# QuadPFets.net
KiCad netlist of a schematic drawn in EAGLE
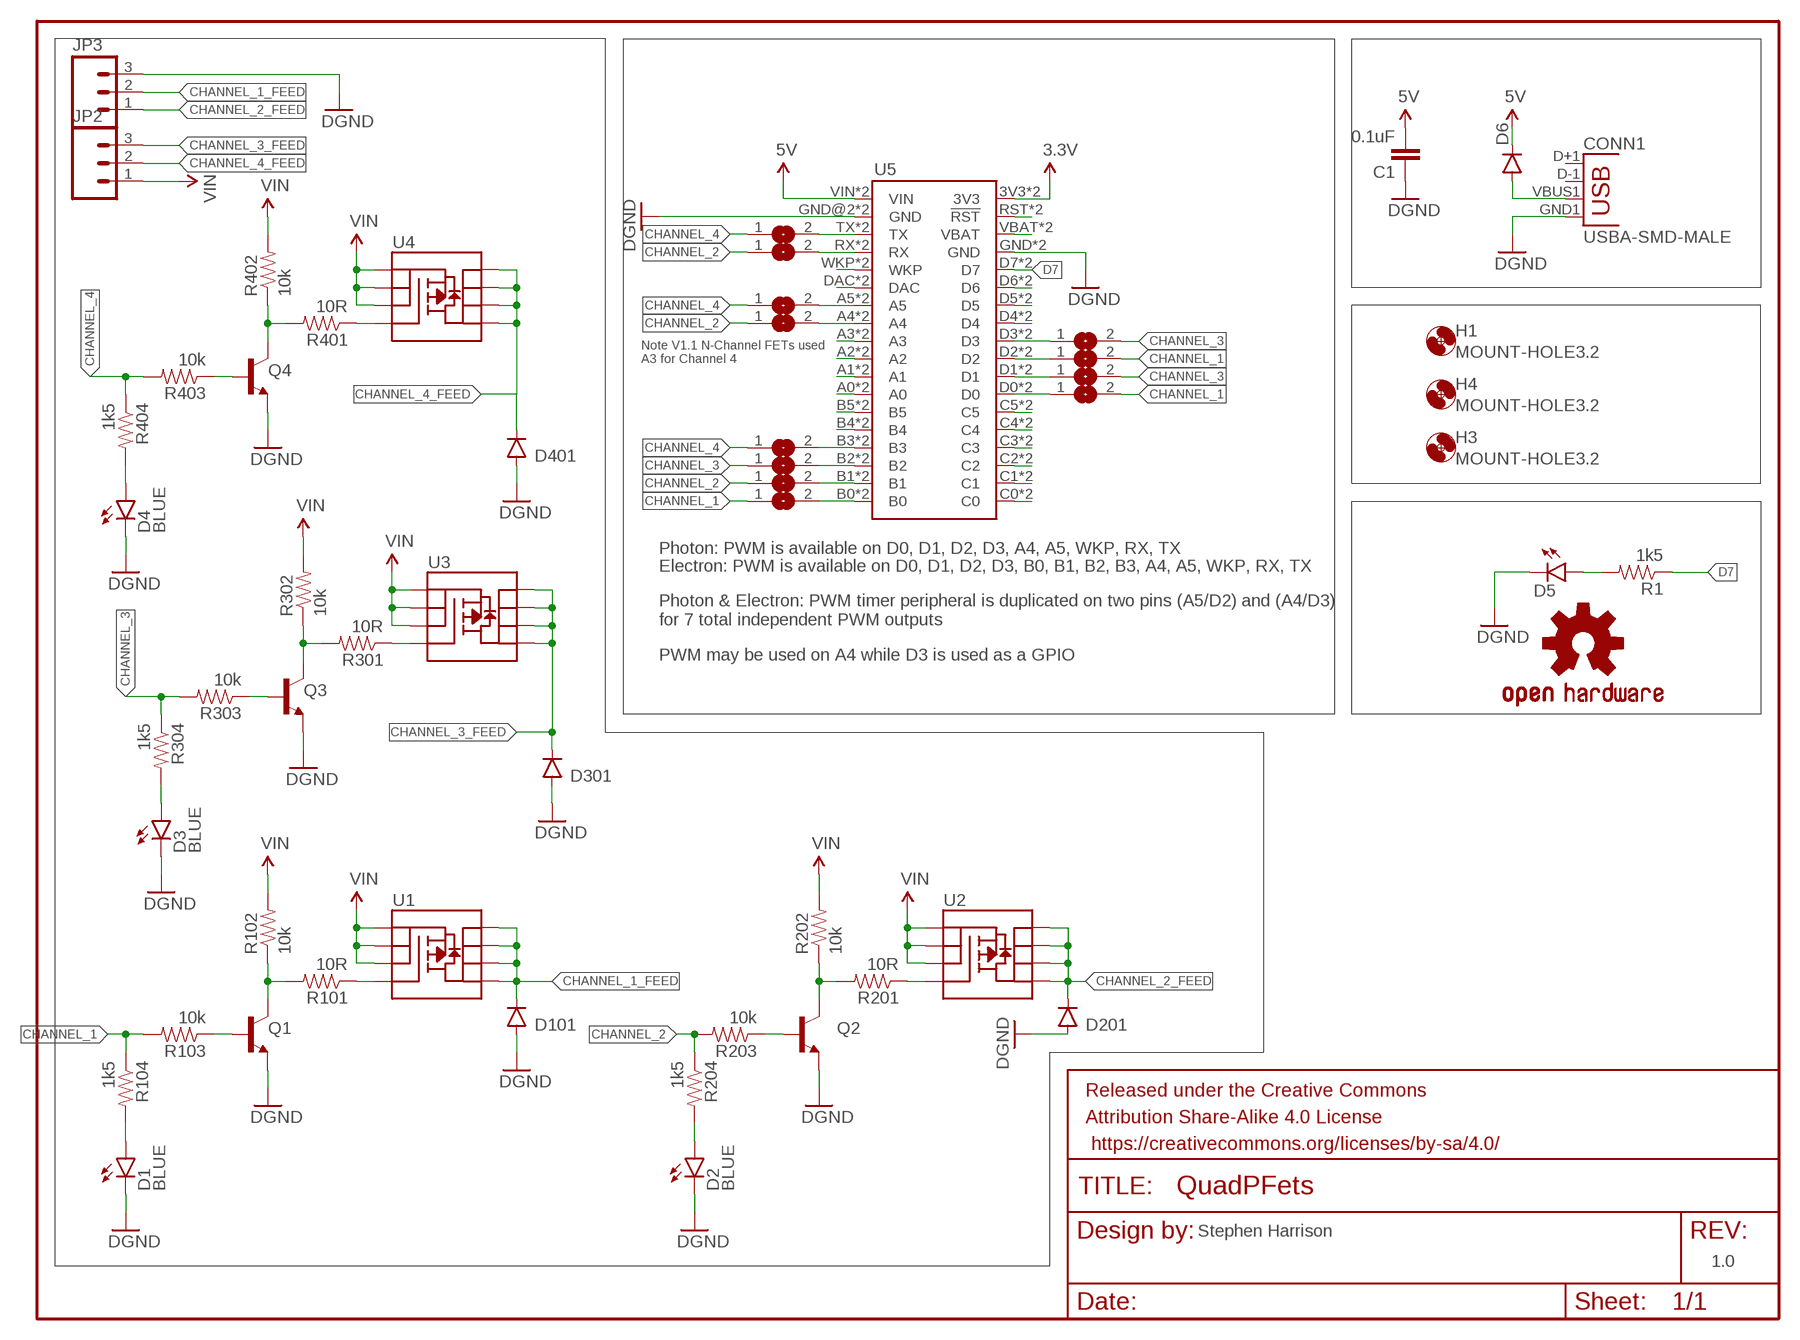
[diagram p0: schematic, sheet 1]

(export (version "E")
  (design (tool "Eeschema 10.0.6"))
  (components
    (comp (ref "C1")
      (value "0.1uF")
      (footprint "eagle-import:0805")
      (libsource (lib "eagle-import") (part "CAP0805"))
    )
    (comp (ref "CONN1")
      (value "USBA-SMD-MALE")
      (footprint "eagle-import:USB-A-SMT-MALE")
      (libsource (lib "eagle-import") (part "USBA-SMD-MALE"))
    )
    (comp (ref "D1")
      (value "BLUE")
      (footprint "eagle-import:LED-1206")
      (libsource (lib "eagle-import") (part "LED-BLUE1206"))
    )
    (comp (ref "D2")
      (value "BLUE")
      (footprint "eagle-import:LED-1206")
      (libsource (lib "eagle-import") (part "LED-BLUE1206"))
    )
    (comp (ref "D3")
      (value "BLUE")
      (footprint "eagle-import:LED-1206")
      (libsource (lib "eagle-import") (part "LED-BLUE1206"))
    )
    (comp (ref "D4")
      (value "BLUE")
      (footprint "eagle-import:LED-1206")
      (libsource (lib "eagle-import") (part "LED-BLUE1206"))
    )
    (comp (ref "D5")
      (value "LED1206-BOTTOM")
      (footprint "eagle-import:LED-1206-BOTTOM")
      (libsource (lib "eagle-import") (part "LED1206-BOTTOM"))
    )
    (comp (ref "D6")
      (value "DIODESMA")
      (footprint "eagle-import:SMA-DIODE")
      (libsource (lib "eagle-import") (part "DIODESMA"))
    )
    (comp (ref "D101")
      (value "DIODESOD123")
      (footprint "eagle-import:SOD-123")
      (libsource (lib "eagle-import") (part "DIODESOD123"))
    )
    (comp (ref "D201")
      (value "DIODESOD123")
      (footprint "eagle-import:SOD-123")
      (libsource (lib "eagle-import") (part "DIODESOD123"))
    )
    (comp (ref "D301")
      (value "DIODESOD123")
      (footprint "eagle-import:SOD-123")
      (libsource (lib "eagle-import") (part "DIODESOD123"))
    )
    (comp (ref "D401")
      (value "DIODESOD123")
      (footprint "eagle-import:SOD-123")
      (libsource (lib "eagle-import") (part "DIODESOD123"))
    )
    (comp (ref "FRAME2")
      (value "FRAME-LETTER")
      (footprint "eagle-import:CREATIVE_COMMONS")
      (libsource (lib "eagle-import") (part "FRAME-LETTER"))
    )
    (comp (ref "H1")
      (value "MOUNT-HOLE3.2")
      (footprint "eagle-import:3,2")
      (libsource (lib "eagle-import") (part "MOUNT-HOLE3.2"))
    )
    (comp (ref "H3")
      (value "MOUNT-HOLE3.2")
      (footprint "eagle-import:3,2")
      (libsource (lib "eagle-import") (part "MOUNT-HOLE3.2"))
    )
    (comp (ref "H4")
      (value "MOUNT-HOLE3.2")
      (footprint "eagle-import:3,2")
      (libsource (lib "eagle-import") (part "MOUNT-HOLE3.2"))
    )
    (comp (ref "JP2")
      (value "M03-SCREW-5MM")
      (footprint "eagle-import:SCREWTERMINAL-5MM-3")
      (libsource (lib "eagle-import") (part "M03-SCREW-5MM"))
    )
    (comp (ref "JP3")
      (value "M03-SCREW-5MM")
      (footprint "eagle-import:SCREWTERMINAL-5MM-3")
      (libsource (lib "eagle-import") (part "M03-SCREW-5MM"))
    )
    (comp (ref "LOGO1")
      (value "OSHW-LOGOM")
      (footprint "eagle-import:OSHW-LOGO-M")
      (libsource (lib "eagle-import") (part "OSHW-LOGOM"))
    )
    (comp (ref "Q1")
      (value "BC817-40SMD")
      (footprint "eagle-import:SOT23-BEC")
      (libsource (lib "eagle-import") (part "BC817SMD-40"))
    )
    (comp (ref "Q2")
      (value "BC817-40SMD")
      (footprint "eagle-import:SOT23-BEC")
      (libsource (lib "eagle-import") (part "BC817SMD-40"))
    )
    (comp (ref "Q3")
      (value "BC817-40SMD")
      (footprint "eagle-import:SOT23-BEC")
      (libsource (lib "eagle-import") (part "BC817SMD-40"))
    )
    (comp (ref "Q4")
      (value "BC817-40SMD")
      (footprint "eagle-import:SOT23-BEC")
      (libsource (lib "eagle-import") (part "BC817SMD-40"))
    )
    (comp (ref "R1")
      (value "1k5")
      (footprint "eagle-import:0805")
      (libsource (lib "eagle-import") (part "RESISTOR0805-RES"))
    )
    (comp (ref "R101")
      (value "10R")
      (footprint "eagle-import:0805")
      (libsource (lib "eagle-import") (part "RESISTOR0805-RES"))
    )
    (comp (ref "R102")
      (value "10k")
      (footprint "eagle-import:0805")
      (libsource (lib "eagle-import") (part "RESISTOR0805-RES"))
    )
    (comp (ref "R103")
      (value "10k")
      (footprint "eagle-import:0805")
      (libsource (lib "eagle-import") (part "RESISTOR0805-RES"))
    )
    (comp (ref "R104")
      (value "1k5")
      (footprint "eagle-import:0805")
      (libsource (lib "eagle-import") (part "RESISTOR0805-RES"))
    )
    (comp (ref "R201")
      (value "10R")
      (footprint "eagle-import:0805")
      (libsource (lib "eagle-import") (part "RESISTOR0805-RES"))
    )
    (comp (ref "R202")
      (value "10k")
      (footprint "eagle-import:0805")
      (libsource (lib "eagle-import") (part "RESISTOR0805-RES"))
    )
    (comp (ref "R203")
      (value "10k")
      (footprint "eagle-import:0805")
      (libsource (lib "eagle-import") (part "RESISTOR0805-RES"))
    )
    (comp (ref "R204")
      (value "1k5")
      (footprint "eagle-import:0805")
      (libsource (lib "eagle-import") (part "RESISTOR0805-RES"))
    )
    (comp (ref "R301")
      (value "10R")
      (footprint "eagle-import:0805")
      (libsource (lib "eagle-import") (part "RESISTOR0805-RES"))
    )
    (comp (ref "R302")
      (value "10k")
      (footprint "eagle-import:0805")
      (libsource (lib "eagle-import") (part "RESISTOR0805-RES"))
    )
    (comp (ref "R303")
      (value "10k")
      (footprint "eagle-import:0805")
      (libsource (lib "eagle-import") (part "RESISTOR0805-RES"))
    )
    (comp (ref "R304")
      (value "1k5")
      (footprint "eagle-import:0805")
      (libsource (lib "eagle-import") (part "RESISTOR0805-RES"))
    )
    (comp (ref "R401")
      (value "10R")
      (footprint "eagle-import:0805")
      (libsource (lib "eagle-import") (part "RESISTOR0805-RES"))
    )
    (comp (ref "R402")
      (value "10k")
      (footprint "eagle-import:0805")
      (libsource (lib "eagle-import") (part "RESISTOR0805-RES"))
    )
    (comp (ref "R403")
      (value "10k")
      (footprint "eagle-import:0805")
      (libsource (lib "eagle-import") (part "RESISTOR0805-RES"))
    )
    (comp (ref "R404")
      (value "1k5")
      (footprint "eagle-import:0805")
      (libsource (lib "eagle-import") (part "RESISTOR0805-RES"))
    )
    (comp (ref "SJ1") (value "SJ") (footprint "eagle-import:SJ") (libsource (lib "eagle-import") (part "SJ")))
    (comp (ref "SJ2") (value "SJ") (footprint "eagle-import:SJ") (libsource (lib "eagle-import") (part "SJ")))
    (comp (ref "SJ3") (value "SJ") (footprint "eagle-import:SJ") (libsource (lib "eagle-import") (part "SJ")))
    (comp (ref "SJ4") (value "SJ") (footprint "eagle-import:SJ") (libsource (lib "eagle-import") (part "SJ")))
    (comp (ref "SJ5") (value "SJ") (footprint "eagle-import:SJ") (libsource (lib "eagle-import") (part "SJ")))
    (comp (ref "SJ6") (value "SJ") (footprint "eagle-import:SJ") (libsource (lib "eagle-import") (part "SJ")))
    (comp (ref "SJ7") (value "SJ") (footprint "eagle-import:SJ") (libsource (lib "eagle-import") (part "SJ")))
    (comp (ref "SJ8") (value "SJ") (footprint "eagle-import:SJ") (libsource (lib "eagle-import") (part "SJ")))
    (comp (ref "SJ9") (value "SJ") (footprint "eagle-import:SJ") (libsource (lib "eagle-import") (part "SJ")))
    (comp (ref "SJ10")
      (value "SJ")
      (footprint "eagle-import:SJ")
      (libsource (lib "eagle-import") (part "SJ"))
    )
    (comp (ref "SJ11")
      (value "SJ")
      (footprint "eagle-import:SJ")
      (libsource (lib "eagle-import") (part "SJ"))
    )
    (comp (ref "SJ12")
      (value "SJ")
      (footprint "eagle-import:SJ")
      (libsource (lib "eagle-import") (part "SJ"))
    )
    (comp (ref "U1")
      (value "MOSFET-PCHANNEL-SOIC8SOIC8")
      (footprint "eagle-import:SO08")
      (libsource (lib "eagle-import") (part "MOSFET-PCHANNEL-SOIC8SOIC8"))
    )
    (comp (ref "U2")
      (value "MOSFET-PCHANNEL-SOIC8SOIC8")
      (footprint "eagle-import:SO08")
      (libsource (lib "eagle-import") (part "MOSFET-PCHANNEL-SOIC8SOIC8"))
    )
    (comp (ref "U3")
      (value "MOSFET-PCHANNEL-SOIC8SOIC8")
      (footprint "eagle-import:SO08")
      (libsource (lib "eagle-import") (part "MOSFET-PCHANNEL-SOIC8SOIC8"))
    )
    (comp (ref "U4")
      (value "MOSFET-PCHANNEL-SOIC8SOIC8")
      (footprint "eagle-import:SO08")
      (libsource (lib "eagle-import") (part "MOSFET-PCHANNEL-SOIC8SOIC8"))
    )
    (comp (ref "U5")
      (value "ELECTRONDUALNAMED")
      (footprint "eagle-import:ELECTRON_SIMPLE_SILK_NAMES_DUAL")
      (libsource (lib "eagle-import") (part "ELECTRONDUALNAMED"))
    )
  )
  (nets
    (net (code "1") (name "3.3V") (class "Default")
      (node (ref "U5") (pin "3V3") (pinfunction "3V3_3V3") (pintype "power_in"))
      (node (ref "U5") (pin "3V3_1") (pinfunction "3V3_3V3_1") (pintype "power_in"))
    )
    (net (code "2") (name "5V") (class "Default")
      (node (ref "C1") (pin "2") (pinfunction "2_2") (pintype "passive"))
      (node (ref "D6") (pin "C") (pinfunction "C_C") (pintype "passive"))
      (node (ref "U5") (pin "VIN") (pinfunction "VIN_VIN") (pintype "power_in"))
      (node (ref "U5") (pin "VIN_1B") (pinfunction "VIN_VIN_1B") (pintype "power_in"))
    )
    (net (code "3") (name "CHANNEL_1") (class "Default")
      (node (ref "R103") (pin "2") (pinfunction "2_2") (pintype "passive"))
      (node (ref "R104") (pin "1") (pinfunction "1_1") (pintype "passive"))
      (node (ref "SJ11") (pin "2") (pinfunction "2_2") (pintype "passive"))
      (node (ref "SJ4") (pin "1") (pinfunction "1_1") (pintype "passive"))
      (node (ref "SJ5") (pin "2") (pinfunction "2_2") (pintype "passive"))
    )
    (net (code "4") (name "CHANNEL_1_FEED") (class "Default")
      (node (ref "D101") (pin "C") (pinfunction "C_C") (pintype "passive"))
      (node (ref "JP3") (pin "2") (pinfunction "2_2") (pintype "passive"))
      (node (ref "U1") (pin "5") (pinfunction "D_5") (pintype "bidirectional"))
      (node (ref "U1") (pin "6") (pinfunction "D_6") (pintype "bidirectional"))
      (node (ref "U1") (pin "7") (pinfunction "D_7") (pintype "bidirectional"))
      (node (ref "U1") (pin "8") (pinfunction "D_8") (pintype "bidirectional"))
    )
    (net (code "5") (name "CHANNEL_2") (class "Default")
      (node (ref "R203") (pin "2") (pinfunction "2_2") (pintype "passive"))
      (node (ref "R204") (pin "1") (pinfunction "1_1") (pintype "passive"))
      (node (ref "SJ10") (pin "1") (pinfunction "1_1") (pintype "passive"))
      (node (ref "SJ3") (pin "1") (pinfunction "1_1") (pintype "passive"))
      (node (ref "SJ8") (pin "1") (pinfunction "1_1") (pintype "passive"))
    )
    (net (code "6") (name "CHANNEL_2_FEED") (class "Default")
      (node (ref "D201") (pin "C") (pinfunction "C_C") (pintype "passive"))
      (node (ref "JP3") (pin "1") (pinfunction "1_1") (pintype "passive"))
      (node (ref "U2") (pin "5") (pinfunction "D_5") (pintype "bidirectional"))
      (node (ref "U2") (pin "6") (pinfunction "D_6") (pintype "bidirectional"))
      (node (ref "U2") (pin "7") (pinfunction "D_7") (pintype "bidirectional"))
      (node (ref "U2") (pin "8") (pinfunction "D_8") (pintype "bidirectional"))
    )
    (net (code "7") (name "CHANNEL_3") (class "Default")
      (node (ref "R303") (pin "2") (pinfunction "2_2") (pintype "passive"))
      (node (ref "R304") (pin "1") (pinfunction "1_1") (pintype "passive"))
      (node (ref "SJ12") (pin "2") (pinfunction "2_2") (pintype "passive"))
      (node (ref "SJ2") (pin "1") (pinfunction "1_1") (pintype "passive"))
      (node (ref "SJ6") (pin "2") (pinfunction "2_2") (pintype "passive"))
    )
    (net (code "8") (name "CHANNEL_3_FEED") (class "Default")
      (node (ref "D301") (pin "C") (pinfunction "C_C") (pintype "passive"))
      (node (ref "JP2") (pin "3") (pinfunction "3_3") (pintype "passive"))
      (node (ref "U3") (pin "5") (pinfunction "D_5") (pintype "bidirectional"))
      (node (ref "U3") (pin "6") (pinfunction "D_6") (pintype "bidirectional"))
      (node (ref "U3") (pin "7") (pinfunction "D_7") (pintype "bidirectional"))
      (node (ref "U3") (pin "8") (pinfunction "D_8") (pintype "bidirectional"))
    )
    (net (code "9") (name "CHANNEL_4") (class "Default")
      (node (ref "R403") (pin "2") (pinfunction "2_2") (pintype "passive"))
      (node (ref "R404") (pin "1") (pinfunction "1_1") (pintype "passive"))
      (node (ref "SJ1") (pin "1") (pinfunction "1_1") (pintype "passive"))
      (node (ref "SJ7") (pin "1") (pinfunction "1_1") (pintype "passive"))
      (node (ref "SJ9") (pin "1") (pinfunction "1_1") (pintype "passive"))
    )
    (net (code "10") (name "CHANNEL_4_FEED") (class "Default")
      (node (ref "D401") (pin "C") (pinfunction "C_C") (pintype "passive"))
      (node (ref "JP2") (pin "2") (pinfunction "2_2") (pintype "passive"))
      (node (ref "U4") (pin "5") (pinfunction "D_5") (pintype "bidirectional"))
      (node (ref "U4") (pin "6") (pinfunction "D_6") (pintype "bidirectional"))
      (node (ref "U4") (pin "7") (pinfunction "D_7") (pintype "bidirectional"))
      (node (ref "U4") (pin "8") (pinfunction "D_8") (pintype "bidirectional"))
    )
    (net (code "11") (name "D7") (class "Default")
      (node (ref "R1") (pin "1") (pinfunction "1_1") (pintype "passive"))
      (node (ref "U5") (pin "D7") (pinfunction "D7_D7") (pintype "bidirectional"))
      (node (ref "U5") (pin "D7_1") (pinfunction "D7_D7_1") (pintype "bidirectional"))
    )
    (net (code "12") (name "DGND") (class "Default")
      (node (ref "C1") (pin "1") (pinfunction "1_1") (pintype "passive"))
      (node (ref "CONN1") (pin "GND1") (pinfunction "GND_GND1") (pintype "bidirectional"))
      (node (ref "D1") (pin "C") (pinfunction "C_C") (pintype "passive"))
      (node (ref "D101") (pin "A") (pinfunction "A_A") (pintype "passive"))
      (node (ref "D2") (pin "C") (pinfunction "C_C") (pintype "passive"))
      (node (ref "D201") (pin "A") (pinfunction "A_A") (pintype "passive"))
      (node (ref "D3") (pin "C") (pinfunction "C_C") (pintype "passive"))
      (node (ref "D301") (pin "A") (pinfunction "A_A") (pintype "passive"))
      (node (ref "D4") (pin "C") (pinfunction "C_C") (pintype "passive"))
      (node (ref "D401") (pin "A") (pinfunction "A_A") (pintype "passive"))
      (node (ref "D5") (pin "C") (pinfunction "C_C") (pintype "passive"))
      (node (ref "JP3") (pin "3") (pinfunction "3_3") (pintype "passive"))
      (node (ref "Q1") (pin "E") (pinfunction "E_E") (pintype "passive"))
      (node (ref "Q2") (pin "E") (pinfunction "E_E") (pintype "passive"))
      (node (ref "Q3") (pin "E") (pinfunction "E_E") (pintype "passive"))
      (node (ref "Q4") (pin "E") (pinfunction "E_E") (pintype "passive"))
      (node (ref "U5") (pin "GND") (pinfunction "GND_GND") (pintype "power_in"))
      (node (ref "U5") (pin "GND@2") (pinfunction "GND_GND@2") (pintype "power_in"))
      (node (ref "U5") (pin "GND_1") (pinfunction "GND_GND_1") (pintype "power_in"))
      (node (ref "U5") (pin "GND_1B") (pinfunction "GND_GND_1B") (pintype "power_in"))
    )
    (net (code "13") (name "Net-(CONN1-VBUS)") (class "Default")
      (node (ref "CONN1") (pin "VBUS1") (pinfunction "VBUS_VBUS1") (pintype "bidirectional"))
      (node (ref "D6") (pin "A") (pinfunction "A_A") (pintype "passive"))
    )
    (net (code "14") (name "Net-(D1-PadA)") (class "Default")
      (node (ref "D1") (pin "A") (pinfunction "A_A") (pintype "passive"))
      (node (ref "R104") (pin "2") (pinfunction "2_2") (pintype "passive"))
    )
    (net (code "15") (name "Net-(D2-PadA)") (class "Default")
      (node (ref "D2") (pin "A") (pinfunction "A_A") (pintype "passive"))
      (node (ref "R204") (pin "2") (pinfunction "2_2") (pintype "passive"))
    )
    (net (code "16") (name "Net-(D3-PadA)") (class "Default")
      (node (ref "D3") (pin "A") (pinfunction "A_A") (pintype "passive"))
      (node (ref "R304") (pin "2") (pinfunction "2_2") (pintype "passive"))
    )
    (net (code "17") (name "Net-(D4-PadA)") (class "Default")
      (node (ref "D4") (pin "A") (pinfunction "A_A") (pintype "passive"))
      (node (ref "R404") (pin "2") (pinfunction "2_2") (pintype "passive"))
    )
    (net (code "18") (name "Net-(D5-PadA)") (class "Default")
      (node (ref "D5") (pin "A") (pinfunction "A_A") (pintype "passive"))
      (node (ref "R1") (pin "2") (pinfunction "2_2") (pintype "passive"))
    )
    (net (code "19") (name "Net-(Q1-PadB)") (class "Default")
      (node (ref "Q1") (pin "B") (pinfunction "B_B") (pintype "passive"))
      (node (ref "R103") (pin "1") (pinfunction "1_1") (pintype "passive"))
    )
    (net (code "20") (name "Net-(Q1-PadC)") (class "Default")
      (node (ref "Q1") (pin "C") (pinfunction "C_C") (pintype "passive"))
      (node (ref "R101") (pin "2") (pinfunction "2_2") (pintype "passive"))
      (node (ref "R102") (pin "1") (pinfunction "1_1") (pintype "passive"))
    )
    (net (code "21") (name "Net-(Q2-PadB)") (class "Default")
      (node (ref "Q2") (pin "B") (pinfunction "B_B") (pintype "passive"))
      (node (ref "R203") (pin "1") (pinfunction "1_1") (pintype "passive"))
    )
    (net (code "22") (name "Net-(Q2-PadC)") (class "Default")
      (node (ref "Q2") (pin "C") (pinfunction "C_C") (pintype "passive"))
      (node (ref "R201") (pin "2") (pinfunction "2_2") (pintype "passive"))
      (node (ref "R202") (pin "1") (pinfunction "1_1") (pintype "passive"))
    )
    (net (code "23") (name "Net-(Q3-PadB)") (class "Default")
      (node (ref "Q3") (pin "B") (pinfunction "B_B") (pintype "passive"))
      (node (ref "R303") (pin "1") (pinfunction "1_1") (pintype "passive"))
    )
    (net (code "24") (name "Net-(Q3-PadC)") (class "Default")
      (node (ref "Q3") (pin "C") (pinfunction "C_C") (pintype "passive"))
      (node (ref "R301") (pin "2") (pinfunction "2_2") (pintype "passive"))
      (node (ref "R302") (pin "1") (pinfunction "1_1") (pintype "passive"))
    )
    (net (code "25") (name "Net-(Q4-PadB)") (class "Default")
      (node (ref "Q4") (pin "B") (pinfunction "B_B") (pintype "passive"))
      (node (ref "R403") (pin "1") (pinfunction "1_1") (pintype "passive"))
    )
    (net (code "26") (name "Net-(Q4-PadC)") (class "Default")
      (node (ref "Q4") (pin "C") (pinfunction "C_C") (pintype "passive"))
      (node (ref "R401") (pin "2") (pinfunction "2_2") (pintype "passive"))
      (node (ref "R402") (pin "1") (pinfunction "1_1") (pintype "passive"))
    )
    (net (code "27") (name "Net-(SJ1-Pad2)") (class "Default")
      (node (ref "SJ1") (pin "2") (pinfunction "2_2") (pintype "passive"))
      (node (ref "U5") (pin "B3") (pinfunction "B3_B3") (pintype "bidirectional"))
      (node (ref "U5") (pin "B3_1") (pinfunction "B3_B3_1") (pintype "bidirectional"))
    )
    (net (code "28") (name "Net-(SJ2-Pad2)") (class "Default")
      (node (ref "SJ2") (pin "2") (pinfunction "2_2") (pintype "passive"))
      (node (ref "U5") (pin "B2") (pinfunction "B2_B2") (pintype "bidirectional"))
      (node (ref "U5") (pin "B2_1") (pinfunction "B2_B2_1") (pintype "bidirectional"))
    )
    (net (code "29") (name "Net-(SJ3-Pad2)") (class "Default")
      (node (ref "SJ3") (pin "2") (pinfunction "2_2") (pintype "passive"))
      (node (ref "U5") (pin "B1") (pinfunction "B1_B1") (pintype "bidirectional"))
      (node (ref "U5") (pin "B1_1") (pinfunction "B1_B1_1") (pintype "bidirectional"))
    )
    (net (code "30") (name "Net-(SJ4-Pad2)") (class "Default")
      (node (ref "SJ4") (pin "2") (pinfunction "2_2") (pintype "passive"))
      (node (ref "U5") (pin "B0") (pinfunction "B0_B0") (pintype "bidirectional"))
      (node (ref "U5") (pin "B0_1") (pinfunction "B0_B0_1") (pintype "bidirectional"))
    )
    (net (code "31") (name "Net-(SJ5-Pad1)") (class "Default")
      (node (ref "SJ5") (pin "1") (pinfunction "1_1") (pintype "passive"))
      (node (ref "U5") (pin "D2") (pinfunction "D2_D2") (pintype "bidirectional"))
      (node (ref "U5") (pin "D2_1") (pinfunction "D2_D2_1") (pintype "bidirectional"))
    )
    (net (code "32") (name "Net-(SJ6-Pad1)") (class "Default")
      (node (ref "SJ6") (pin "1") (pinfunction "1_1") (pintype "passive"))
      (node (ref "U5") (pin "D3") (pinfunction "D3_D3") (pintype "bidirectional"))
      (node (ref "U5") (pin "D3_1") (pinfunction "D3_D3_1") (pintype "bidirectional"))
    )
    (net (code "33") (name "Net-(SJ7-Pad2)") (class "Default")
      (node (ref "SJ7") (pin "2") (pinfunction "2_2") (pintype "passive"))
      (node (ref "U5") (pin "TX") (pinfunction "TX_TX") (pintype "bidirectional"))
      (node (ref "U5") (pin "TX_1") (pinfunction "TX_TX_1") (pintype "bidirectional"))
    )
    (net (code "34") (name "Net-(SJ8-Pad2)") (class "Default")
      (node (ref "SJ8") (pin "2") (pinfunction "2_2") (pintype "passive"))
      (node (ref "U5") (pin "A4") (pinfunction "A4_A4") (pintype "bidirectional"))
      (node (ref "U5") (pin "A4_1") (pinfunction "A4_A4_1") (pintype "bidirectional"))
    )
    (net (code "35") (name "Net-(SJ9-Pad2)") (class "Default")
      (node (ref "SJ9") (pin "2") (pinfunction "2_2") (pintype "passive"))
      (node (ref "U5") (pin "A5") (pinfunction "A5_A5") (pintype "bidirectional"))
      (node (ref "U5") (pin "A5_1") (pinfunction "A5_A5_1") (pintype "bidirectional"))
    )
    (net (code "36") (name "Net-(SJ10-Pad2)") (class "Default")
      (node (ref "SJ10") (pin "2") (pinfunction "2_2") (pintype "passive"))
      (node (ref "U5") (pin "RX") (pinfunction "RX_RX") (pintype "bidirectional"))
      (node (ref "U5") (pin "RX_1") (pinfunction "RX_RX_1") (pintype "bidirectional"))
    )
    (net (code "37") (name "Net-(SJ11-Pad1)") (class "Default")
      (node (ref "SJ11") (pin "1") (pinfunction "1_1") (pintype "passive"))
      (node (ref "U5") (pin "D0") (pinfunction "D0_D0") (pintype "bidirectional"))
      (node (ref "U5") (pin "D0_1") (pinfunction "D0_D0_1") (pintype "bidirectional"))
    )
    (net (code "38") (name "Net-(SJ12-Pad1)") (class "Default")
      (node (ref "SJ12") (pin "1") (pinfunction "1_1") (pintype "passive"))
      (node (ref "U5") (pin "D1") (pinfunction "D1_D1") (pintype "bidirectional"))
      (node (ref "U5") (pin "D1_1") (pinfunction "D1_D1_1") (pintype "bidirectional"))
    )
    (net (code "39") (name "Net-(U1-G)") (class "Default")
      (node (ref "R101") (pin "1") (pinfunction "1_1") (pintype "passive"))
      (node (ref "U1") (pin "4") (pinfunction "G_4") (pintype "bidirectional"))
    )
    (net (code "40") (name "Net-(U2-G)") (class "Default")
      (node (ref "R201") (pin "1") (pinfunction "1_1") (pintype "passive"))
      (node (ref "U2") (pin "4") (pinfunction "G_4") (pintype "bidirectional"))
    )
    (net (code "41") (name "Net-(U3-G)") (class "Default")
      (node (ref "R301") (pin "1") (pinfunction "1_1") (pintype "passive"))
      (node (ref "U3") (pin "4") (pinfunction "G_4") (pintype "bidirectional"))
    )
    (net (code "42") (name "Net-(U4-G)") (class "Default")
      (node (ref "R401") (pin "1") (pinfunction "1_1") (pintype "passive"))
      (node (ref "U4") (pin "4") (pinfunction "G_4") (pintype "bidirectional"))
    )
    (net (code "43") (name "Net-(U5-A0-PadA0_1)") (class "Default")
      (node (ref "U5") (pin "A0") (pinfunction "A0_A0") (pintype "bidirectional"))
      (node (ref "U5") (pin "A0_1") (pinfunction "A0_A0_1") (pintype "bidirectional"))
    )
    (net (code "44") (name "Net-(U5-A1-PadA1_1)") (class "Default")
      (node (ref "U5") (pin "A1") (pinfunction "A1_A1") (pintype "bidirectional"))
      (node (ref "U5") (pin "A1_1") (pinfunction "A1_A1_1") (pintype "bidirectional"))
    )
    (net (code "45") (name "Net-(U5-A2-PadA2_1)") (class "Default")
      (node (ref "U5") (pin "A2") (pinfunction "A2_A2") (pintype "bidirectional"))
      (node (ref "U5") (pin "A2_1") (pinfunction "A2_A2_1") (pintype "bidirectional"))
    )
    (net (code "46") (name "Net-(U5-A3-PadA3_1)") (class "Default")
      (node (ref "U5") (pin "A3") (pinfunction "A3_A3") (pintype "bidirectional"))
      (node (ref "U5") (pin "A3_1") (pinfunction "A3_A3_1") (pintype "bidirectional"))
    )
    (net (code "47") (name "Net-(U5-B4-PadB4_1)") (class "Default")
      (node (ref "U5") (pin "B4") (pinfunction "B4_B4") (pintype "bidirectional"))
      (node (ref "U5") (pin "B4_1") (pinfunction "B4_B4_1") (pintype "bidirectional"))
    )
    (net (code "48") (name "Net-(U5-B5-PadB5_1)") (class "Default")
      (node (ref "U5") (pin "B5") (pinfunction "B5_B5") (pintype "bidirectional"))
      (node (ref "U5") (pin "B5_1") (pinfunction "B5_B5_1") (pintype "bidirectional"))
    )
    (net (code "49") (name "Net-(U5-C0-PadC0_1)") (class "Default")
      (node (ref "U5") (pin "C0") (pinfunction "C0_C0") (pintype "bidirectional"))
      (node (ref "U5") (pin "C0_1") (pinfunction "C0_C0_1") (pintype "bidirectional"))
    )
    (net (code "50") (name "Net-(U5-C1-PadC1_1)") (class "Default")
      (node (ref "U5") (pin "C1") (pinfunction "C1_C1") (pintype "bidirectional"))
      (node (ref "U5") (pin "C1_1") (pinfunction "C1_C1_1") (pintype "bidirectional"))
    )
    (net (code "51") (name "Net-(U5-C2-PadC2_1)") (class "Default")
      (node (ref "U5") (pin "C2") (pinfunction "C2_C2") (pintype "bidirectional"))
      (node (ref "U5") (pin "C2_1") (pinfunction "C2_C2_1") (pintype "bidirectional"))
    )
    (net (code "52") (name "Net-(U5-C3-PadC3_1)") (class "Default")
      (node (ref "U5") (pin "C3") (pinfunction "C3_C3") (pintype "bidirectional"))
      (node (ref "U5") (pin "C3_1") (pinfunction "C3_C3_1") (pintype "bidirectional"))
    )
    (net (code "53") (name "Net-(U5-C4-PadC4_1)") (class "Default")
      (node (ref "U5") (pin "C4") (pinfunction "C4_C4") (pintype "bidirectional"))
      (node (ref "U5") (pin "C4_1") (pinfunction "C4_C4_1") (pintype "bidirectional"))
    )
    (net (code "54") (name "Net-(U5-C5-PadC5_1)") (class "Default")
      (node (ref "U5") (pin "C5") (pinfunction "C5_C5") (pintype "bidirectional"))
      (node (ref "U5") (pin "C5_1") (pinfunction "C5_C5_1") (pintype "bidirectional"))
    )
    (net (code "55") (name "Net-(U5-D4-PadD4_1)") (class "Default")
      (node (ref "U5") (pin "D4") (pinfunction "D4_D4") (pintype "bidirectional"))
      (node (ref "U5") (pin "D4_1") (pinfunction "D4_D4_1") (pintype "bidirectional"))
    )
    (net (code "56") (name "Net-(U5-D5-PadD5_1)") (class "Default")
      (node (ref "U5") (pin "D5") (pinfunction "D5_D5") (pintype "bidirectional"))
      (node (ref "U5") (pin "D5_1") (pinfunction "D5_D5_1") (pintype "bidirectional"))
    )
    (net (code "57") (name "Net-(U5-D6-PadD6_1)") (class "Default")
      (node (ref "U5") (pin "D6") (pinfunction "D6_D6") (pintype "bidirectional"))
      (node (ref "U5") (pin "D6_1") (pinfunction "D6_D6_1") (pintype "bidirectional"))
    )
    (net (code "58") (name "Net-(U5-DAC-PadDAC_1)") (class "Default")
      (node (ref "U5") (pin "DAC") (pinfunction "DAC_DAC") (pintype "bidirectional"))
      (node (ref "U5") (pin "DAC_1") (pinfunction "DAC_DAC_1") (pintype "bidirectional"))
    )
    (net (code "59") (name "Net-(U5-PadVBAT)") (class "Default")
      (node (ref "U5") (pin "VBAT") (pinfunction "VBAT_VBAT") (pintype "passive"))
      (node (ref "U5") (pin "VBATT_1") (pinfunction "VBAT_VBATT_1") (pintype "passive"))
    )
    (net (code "60") (name "Net-(U5-PadWKP)") (class "Default")
      (node (ref "U5") (pin "WKP") (pinfunction "WKP_WKP") (pintype "bidirectional"))
      (node (ref "U5") (pin "WKP_1") (pinfunction "WKP_WKP_1") (pintype "bidirectional"))
    )
    (net (code "61") (name "Net-(U5-~{RST}-PadRST)") (class "Default")
      (node (ref "U5") (pin "RST") (pinfunction "~{RST}_RST") (pintype "bidirectional"))
      (node (ref "U5") (pin "RST_1") (pinfunction "~{RST}_RST_1") (pintype "bidirectional"))
    )
    (net (code "62") (name "VIN") (class "Default")
      (node (ref "JP2") (pin "1") (pinfunction "1_1") (pintype "passive"))
      (node (ref "R102") (pin "2") (pinfunction "2_2") (pintype "passive"))
      (node (ref "R202") (pin "2") (pinfunction "2_2") (pintype "passive"))
      (node (ref "R302") (pin "2") (pinfunction "2_2") (pintype "passive"))
      (node (ref "R402") (pin "2") (pinfunction "2_2") (pintype "passive"))
      (node (ref "U1") (pin "1") (pinfunction "S_1") (pintype "bidirectional"))
      (node (ref "U1") (pin "2") (pinfunction "S_2") (pintype "bidirectional"))
      (node (ref "U1") (pin "3") (pinfunction "S_3") (pintype "bidirectional"))
      (node (ref "U2") (pin "1") (pinfunction "S_1") (pintype "bidirectional"))
      (node (ref "U2") (pin "2") (pinfunction "S_2") (pintype "bidirectional"))
      (node (ref "U2") (pin "3") (pinfunction "S_3") (pintype "bidirectional"))
      (node (ref "U3") (pin "1") (pinfunction "S_1") (pintype "bidirectional"))
      (node (ref "U3") (pin "2") (pinfunction "S_2") (pintype "bidirectional"))
      (node (ref "U3") (pin "3") (pinfunction "S_3") (pintype "bidirectional"))
      (node (ref "U4") (pin "1") (pinfunction "S_1") (pintype "bidirectional"))
      (node (ref "U4") (pin "2") (pinfunction "S_2") (pintype "bidirectional"))
      (node (ref "U4") (pin "3") (pinfunction "S_3") (pintype "bidirectional"))
    )
    (net (code "63") (name "unconnected-(CONN1-D+-PadD+1)") (class "Default")
      (node (ref "CONN1") (pin "D+1") (pinfunction "D+_D+1") (pintype "bidirectional"))
    )
    (net (code "64") (name "unconnected-(CONN1-D--PadD-1)") (class "Default")
      (node (ref "CONN1") (pin "D-1") (pinfunction "D-_D-1") (pintype "bidirectional"))
    )
  )
)
